# gate.net
KiCad netlist of a schematic drawn in Altium Designer
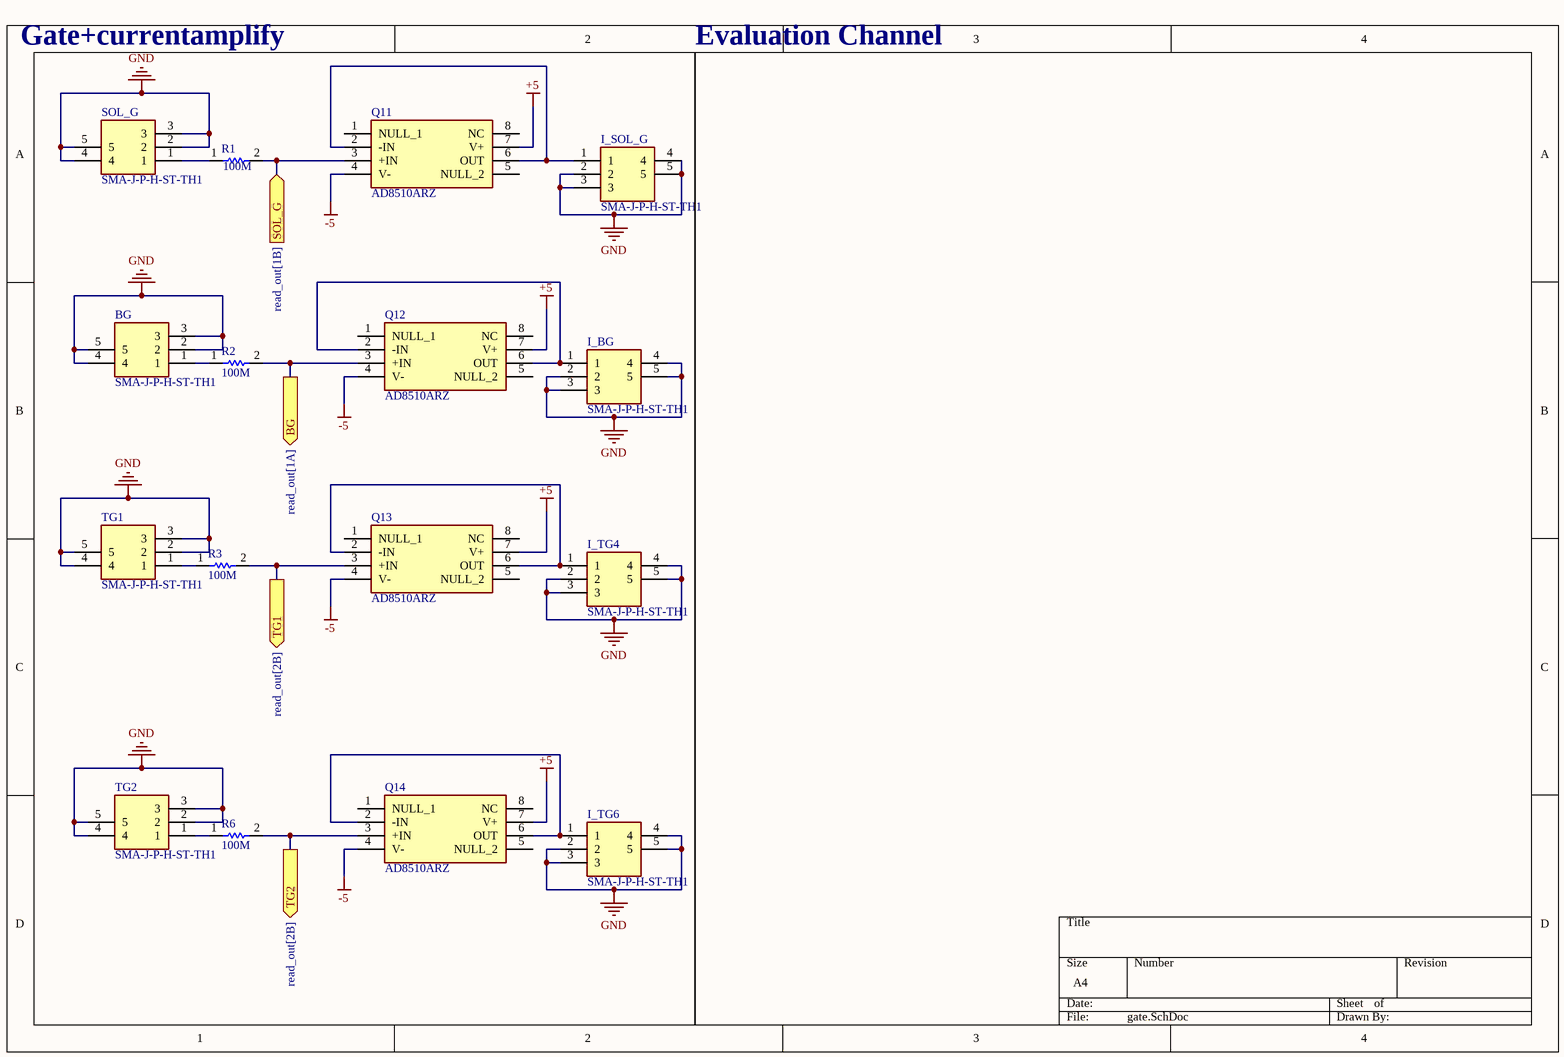
[diagram p0: gate.SchDoc]

(export (version "E")
  (design (tool "Eeschema 10.0.6"))
  (components
    (comp (ref "BG")
      (value "SMA-J-P-H-ST-TH1")
      (footprint "SMAJPHSTTH1")
      (description "SAMTEC - SMA-J-P-H-ST-TH1 - RF COAXIAL, SMA JACK, 50 OHM, PCB")
      (fields (field (name "MOUSER PART NUMBER") "200-SMAJPHSTTH1"))
      (libsource (lib "Schlib1") (part "SMA-J-P-H-ST-TH1"))
    )
    (comp (ref "I_BG")
      (value "SMA-J-P-H-ST-TH1")
      (footprint "SMAJPHSTTH1")
      (description "SAMTEC - SMA-J-P-H-ST-TH1 - RF COAXIAL, SMA JACK, 50 OHM, PCB")
      (fields (field (name "MOUSER PART NUMBER") "200-SMAJPHSTTH1"))
      (libsource (lib "") (part "SMA-J-P-H-ST-TH1_1"))
    )
    (comp (ref "I_SOL_G")
      (value "SMA-J-P-H-ST-TH1")
      (footprint "SMAJPHSTTH1")
      (description "SAMTEC - SMA-J-P-H-ST-TH1 - RF COAXIAL, SMA JACK, 50 OHM, PCB")
      (fields (field (name "MOUSER PART NUMBER") "200-SMAJPHSTTH1"))
      (libsource (lib "") (part "SMA-J-P-H-ST-TH1_1"))
    )
    (comp (ref "I_TG4")
      (value "SMA-J-P-H-ST-TH1")
      (footprint "SMAJPHSTTH1")
      (description "SAMTEC - SMA-J-P-H-ST-TH1 - RF COAXIAL, SMA JACK, 50 OHM, PCB")
      (fields (field (name "MOUSER PART NUMBER") "200-SMAJPHSTTH1"))
      (libsource (lib "") (part "SMA-J-P-H-ST-TH1_1"))
    )
    (comp (ref "I_TG6")
      (value "SMA-J-P-H-ST-TH1")
      (footprint "SMAJPHSTTH1")
      (description "SAMTEC - SMA-J-P-H-ST-TH1 - RF COAXIAL, SMA JACK, 50 OHM, PCB")
      (fields (field (name "MOUSER PART NUMBER") "200-SMAJPHSTTH1"))
      (libsource (lib "") (part "SMA-J-P-H-ST-TH1_1"))
    )
    (comp (ref "Q11")
      (value "AD8510ARZ")
      (footprint "AD8510ARZ")
      (libsource (lib "Schlib1") (part "AD8510ARZ"))
    )
    (comp (ref "Q12")
      (value "AD8510ARZ")
      (footprint "AD8510ARZ")
      (libsource (lib "Schlib1") (part "AD8510ARZ"))
    )
    (comp (ref "Q13")
      (value "AD8510ARZ")
      (footprint "AD8510ARZ")
      (libsource (lib "Schlib1") (part "AD8510ARZ"))
    )
    (comp (ref "Q14")
      (value "AD8510ARZ")
      (footprint "AD8510ARZ")
      (libsource (lib "Schlib1") (part "AD8510ARZ"))
    )
    (comp (ref "R1")
      (value "100M")
      (footprint "CR0805-FX-1543ELF")
      (libsource (lib "Schlib1") (part "resistor"))
    )
    (comp (ref "R2")
      (value "100M")
      (footprint "CR0805-FX-1543ELF")
      (libsource (lib "Schlib1") (part "resistor"))
    )
    (comp (ref "R3")
      (value "100M")
      (footprint "CR0805-FX-1543ELF")
      (libsource (lib "Schlib1") (part "resistor"))
    )
    (comp (ref "R6")
      (value "100M")
      (footprint "CR0805-FX-1543ELF")
      (libsource (lib "Schlib1") (part "resistor"))
    )
    (comp (ref "SOL_G")
      (value "SMA-J-P-H-ST-TH1")
      (footprint "SMAJPHSTTH1")
      (description "SAMTEC - SMA-J-P-H-ST-TH1 - RF COAXIAL, SMA JACK, 50 OHM, PCB")
      (fields (field (name "MOUSER PART NUMBER") "200-SMAJPHSTTH1"))
      (libsource (lib "Schlib1") (part "SMA-J-P-H-ST-TH1"))
    )
    (comp (ref "TG1")
      (value "SMA-J-P-H-ST-TH1")
      (footprint "SMAJPHSTTH1")
      (description "SAMTEC - SMA-J-P-H-ST-TH1 - RF COAXIAL, SMA JACK, 50 OHM, PCB")
      (fields (field (name "MOUSER PART NUMBER") "200-SMAJPHSTTH1"))
      (libsource (lib "Schlib1") (part "SMA-J-P-H-ST-TH1"))
    )
    (comp (ref "TG2")
      (value "SMA-J-P-H-ST-TH1")
      (footprint "SMAJPHSTTH1")
      (description "SAMTEC - SMA-J-P-H-ST-TH1 - RF COAXIAL, SMA JACK, 50 OHM, PCB")
      (fields (field (name "MOUSER PART NUMBER") "200-SMAJPHSTTH1"))
      (libsource (lib "Schlib1") (part "SMA-J-P-H-ST-TH1"))
    )
  )
  (nets
    (net (code "1") (name "+5") (class "Default")
      (node (ref "Q11") (pin "7") (pinfunction "V+_7") (pintype "passive"))
      (node (ref "Q12") (pin "7") (pinfunction "V+_7") (pintype "passive"))
      (node (ref "Q13") (pin "7") (pinfunction "V+_7") (pintype "passive"))
      (node (ref "Q14") (pin "7") (pinfunction "V+_7") (pintype "passive"))
    )
    (net (code "2") (name "-5") (class "Default")
      (node (ref "Q11") (pin "4") (pinfunction "V-_4") (pintype "passive"))
      (node (ref "Q12") (pin "4") (pinfunction "V-_4") (pintype "passive"))
      (node (ref "Q13") (pin "4") (pinfunction "V-_4") (pintype "passive"))
      (node (ref "Q14") (pin "4") (pinfunction "V-_4") (pintype "passive"))
    )
    (net (code "3") (name "/BG") (class "Default")
      (node (ref "Q12") (pin "3") (pinfunction "+IN_3") (pintype "passive"))
      (node (ref "R2") (pin "2") (pinfunction "2_2") (pintype "passive"))
    )
    (net (code "4") (name "/SOL_G") (class "Default")
      (node (ref "Q11") (pin "3") (pinfunction "+IN_3") (pintype "passive"))
      (node (ref "R1") (pin "2") (pinfunction "2_2") (pintype "passive"))
    )
    (net (code "5") (name "/TG1") (class "Default")
      (node (ref "Q13") (pin "3") (pinfunction "+IN_3") (pintype "passive"))
      (node (ref "R3") (pin "2") (pinfunction "2_2") (pintype "passive"))
    )
    (net (code "6") (name "/TG2") (class "Default")
      (node (ref "Q14") (pin "3") (pinfunction "+IN_3") (pintype "passive"))
      (node (ref "R6") (pin "2") (pinfunction "2_2") (pintype "passive"))
    )
    (net (code "7") (name "GND") (class "Default")
      (node (ref "BG") (pin "2") (pinfunction "2_2") (pintype "passive"))
      (node (ref "BG") (pin "3") (pinfunction "3_3") (pintype "passive"))
      (node (ref "BG") (pin "4") (pinfunction "4_4") (pintype "passive"))
      (node (ref "BG") (pin "5") (pinfunction "5_5") (pintype "passive"))
      (node (ref "I_BG") (pin "2") (pinfunction "2_2") (pintype "passive"))
      (node (ref "I_BG") (pin "3") (pinfunction "3_3") (pintype "passive"))
      (node (ref "I_BG") (pin "4") (pinfunction "4_4") (pintype "passive"))
      (node (ref "I_BG") (pin "5") (pinfunction "5_5") (pintype "passive"))
      (node (ref "I_SOL_G") (pin "2") (pinfunction "2_2") (pintype "passive"))
      (node (ref "I_SOL_G") (pin "3") (pinfunction "3_3") (pintype "passive"))
      (node (ref "I_SOL_G") (pin "4") (pinfunction "4_4") (pintype "passive"))
      (node (ref "I_SOL_G") (pin "5") (pinfunction "5_5") (pintype "passive"))
      (node (ref "I_TG4") (pin "2") (pinfunction "2_2") (pintype "passive"))
      (node (ref "I_TG4") (pin "3") (pinfunction "3_3") (pintype "passive"))
      (node (ref "I_TG4") (pin "4") (pinfunction "4_4") (pintype "passive"))
      (node (ref "I_TG4") (pin "5") (pinfunction "5_5") (pintype "passive"))
      (node (ref "I_TG6") (pin "2") (pinfunction "2_2") (pintype "passive"))
      (node (ref "I_TG6") (pin "3") (pinfunction "3_3") (pintype "passive"))
      (node (ref "I_TG6") (pin "4") (pinfunction "4_4") (pintype "passive"))
      (node (ref "I_TG6") (pin "5") (pinfunction "5_5") (pintype "passive"))
      (node (ref "SOL_G") (pin "2") (pinfunction "2_2") (pintype "passive"))
      (node (ref "SOL_G") (pin "3") (pinfunction "3_3") (pintype "passive"))
      (node (ref "SOL_G") (pin "4") (pinfunction "4_4") (pintype "passive"))
      (node (ref "SOL_G") (pin "5") (pinfunction "5_5") (pintype "passive"))
      (node (ref "TG1") (pin "2") (pinfunction "2_2") (pintype "passive"))
      (node (ref "TG1") (pin "3") (pinfunction "3_3") (pintype "passive"))
      (node (ref "TG1") (pin "4") (pinfunction "4_4") (pintype "passive"))
      (node (ref "TG1") (pin "5") (pinfunction "5_5") (pintype "passive"))
      (node (ref "TG2") (pin "2") (pinfunction "2_2") (pintype "passive"))
      (node (ref "TG2") (pin "3") (pinfunction "3_3") (pintype "passive"))
      (node (ref "TG2") (pin "4") (pinfunction "4_4") (pintype "passive"))
      (node (ref "TG2") (pin "5") (pinfunction "5_5") (pintype "passive"))
    )
    (net (code "8") (name "Net-(BG-Pad1)") (class "Default")
      (node (ref "BG") (pin "1") (pinfunction "1_1") (pintype "passive"))
      (node (ref "R2") (pin "1") (pinfunction "1_1") (pintype "passive"))
    )
    (net (code "9") (name "Net-(Q11--IN)") (class "Default")
      (node (ref "I_SOL_G") (pin "1") (pinfunction "1_1") (pintype "passive"))
      (node (ref "Q11") (pin "2") (pinfunction "-IN_2") (pintype "passive"))
      (node (ref "Q11") (pin "6") (pinfunction "OUT_6") (pintype "passive"))
    )
    (net (code "10") (name "Net-(Q12--IN)") (class "Default")
      (node (ref "I_BG") (pin "1") (pinfunction "1_1") (pintype "passive"))
      (node (ref "Q12") (pin "2") (pinfunction "-IN_2") (pintype "passive"))
      (node (ref "Q12") (pin "6") (pinfunction "OUT_6") (pintype "passive"))
    )
    (net (code "11") (name "Net-(Q13--IN)") (class "Default")
      (node (ref "I_TG4") (pin "1") (pinfunction "1_1") (pintype "passive"))
      (node (ref "Q13") (pin "2") (pinfunction "-IN_2") (pintype "passive"))
      (node (ref "Q13") (pin "6") (pinfunction "OUT_6") (pintype "passive"))
    )
    (net (code "12") (name "Net-(Q14--IN)") (class "Default")
      (node (ref "I_TG6") (pin "1") (pinfunction "1_1") (pintype "passive"))
      (node (ref "Q14") (pin "2") (pinfunction "-IN_2") (pintype "passive"))
      (node (ref "Q14") (pin "6") (pinfunction "OUT_6") (pintype "passive"))
    )
    (net (code "13") (name "Net-(R1-Pad1)") (class "Default")
      (node (ref "R1") (pin "1") (pinfunction "1_1") (pintype "passive"))
      (node (ref "SOL_G") (pin "1") (pinfunction "1_1") (pintype "passive"))
    )
    (net (code "14") (name "Net-(R3-Pad1)") (class "Default")
      (node (ref "R3") (pin "1") (pinfunction "1_1") (pintype "passive"))
      (node (ref "TG1") (pin "1") (pinfunction "1_1") (pintype "passive"))
    )
    (net (code "15") (name "Net-(R6-Pad1)") (class "Default")
      (node (ref "R6") (pin "1") (pinfunction "1_1") (pintype "passive"))
      (node (ref "TG2") (pin "1") (pinfunction "1_1") (pintype "passive"))
    )
    (net (code "16") (name "unconnected-(Q11-NC-Pad8)") (class "Default")
      (node (ref "Q11") (pin "8") (pinfunction "NC_8") (pintype "passive"))
    )
    (net (code "17") (name "unconnected-(Q11-NULL_1-Pad1)") (class "Default")
      (node (ref "Q11") (pin "1") (pinfunction "NULL_1_1") (pintype "passive"))
    )
    (net (code "18") (name "unconnected-(Q11-NULL_2-Pad5)") (class "Default")
      (node (ref "Q11") (pin "5") (pinfunction "NULL_2_5") (pintype "passive"))
    )
    (net (code "19") (name "unconnected-(Q12-NC-Pad8)") (class "Default")
      (node (ref "Q12") (pin "8") (pinfunction "NC_8") (pintype "passive"))
    )
    (net (code "20") (name "unconnected-(Q12-NULL_1-Pad1)") (class "Default")
      (node (ref "Q12") (pin "1") (pinfunction "NULL_1_1") (pintype "passive"))
    )
    (net (code "21") (name "unconnected-(Q12-NULL_2-Pad5)") (class "Default")
      (node (ref "Q12") (pin "5") (pinfunction "NULL_2_5") (pintype "passive"))
    )
    (net (code "22") (name "unconnected-(Q13-NC-Pad8)") (class "Default")
      (node (ref "Q13") (pin "8") (pinfunction "NC_8") (pintype "passive"))
    )
    (net (code "23") (name "unconnected-(Q13-NULL_1-Pad1)") (class "Default")
      (node (ref "Q13") (pin "1") (pinfunction "NULL_1_1") (pintype "passive"))
    )
    (net (code "24") (name "unconnected-(Q13-NULL_2-Pad5)") (class "Default")
      (node (ref "Q13") (pin "5") (pinfunction "NULL_2_5") (pintype "passive"))
    )
    (net (code "25") (name "unconnected-(Q14-NC-Pad8)") (class "Default")
      (node (ref "Q14") (pin "8") (pinfunction "NC_8") (pintype "passive"))
    )
    (net (code "26") (name "unconnected-(Q14-NULL_1-Pad1)") (class "Default")
      (node (ref "Q14") (pin "1") (pinfunction "NULL_1_1") (pintype "passive"))
    )
    (net (code "27") (name "unconnected-(Q14-NULL_2-Pad5)") (class "Default")
      (node (ref "Q14") (pin "5") (pinfunction "NULL_2_5") (pintype "passive"))
    )
  )
)
